# ASCII_14_Clocks.net
KiCad netlist of a schematic drawn in Altium Designer
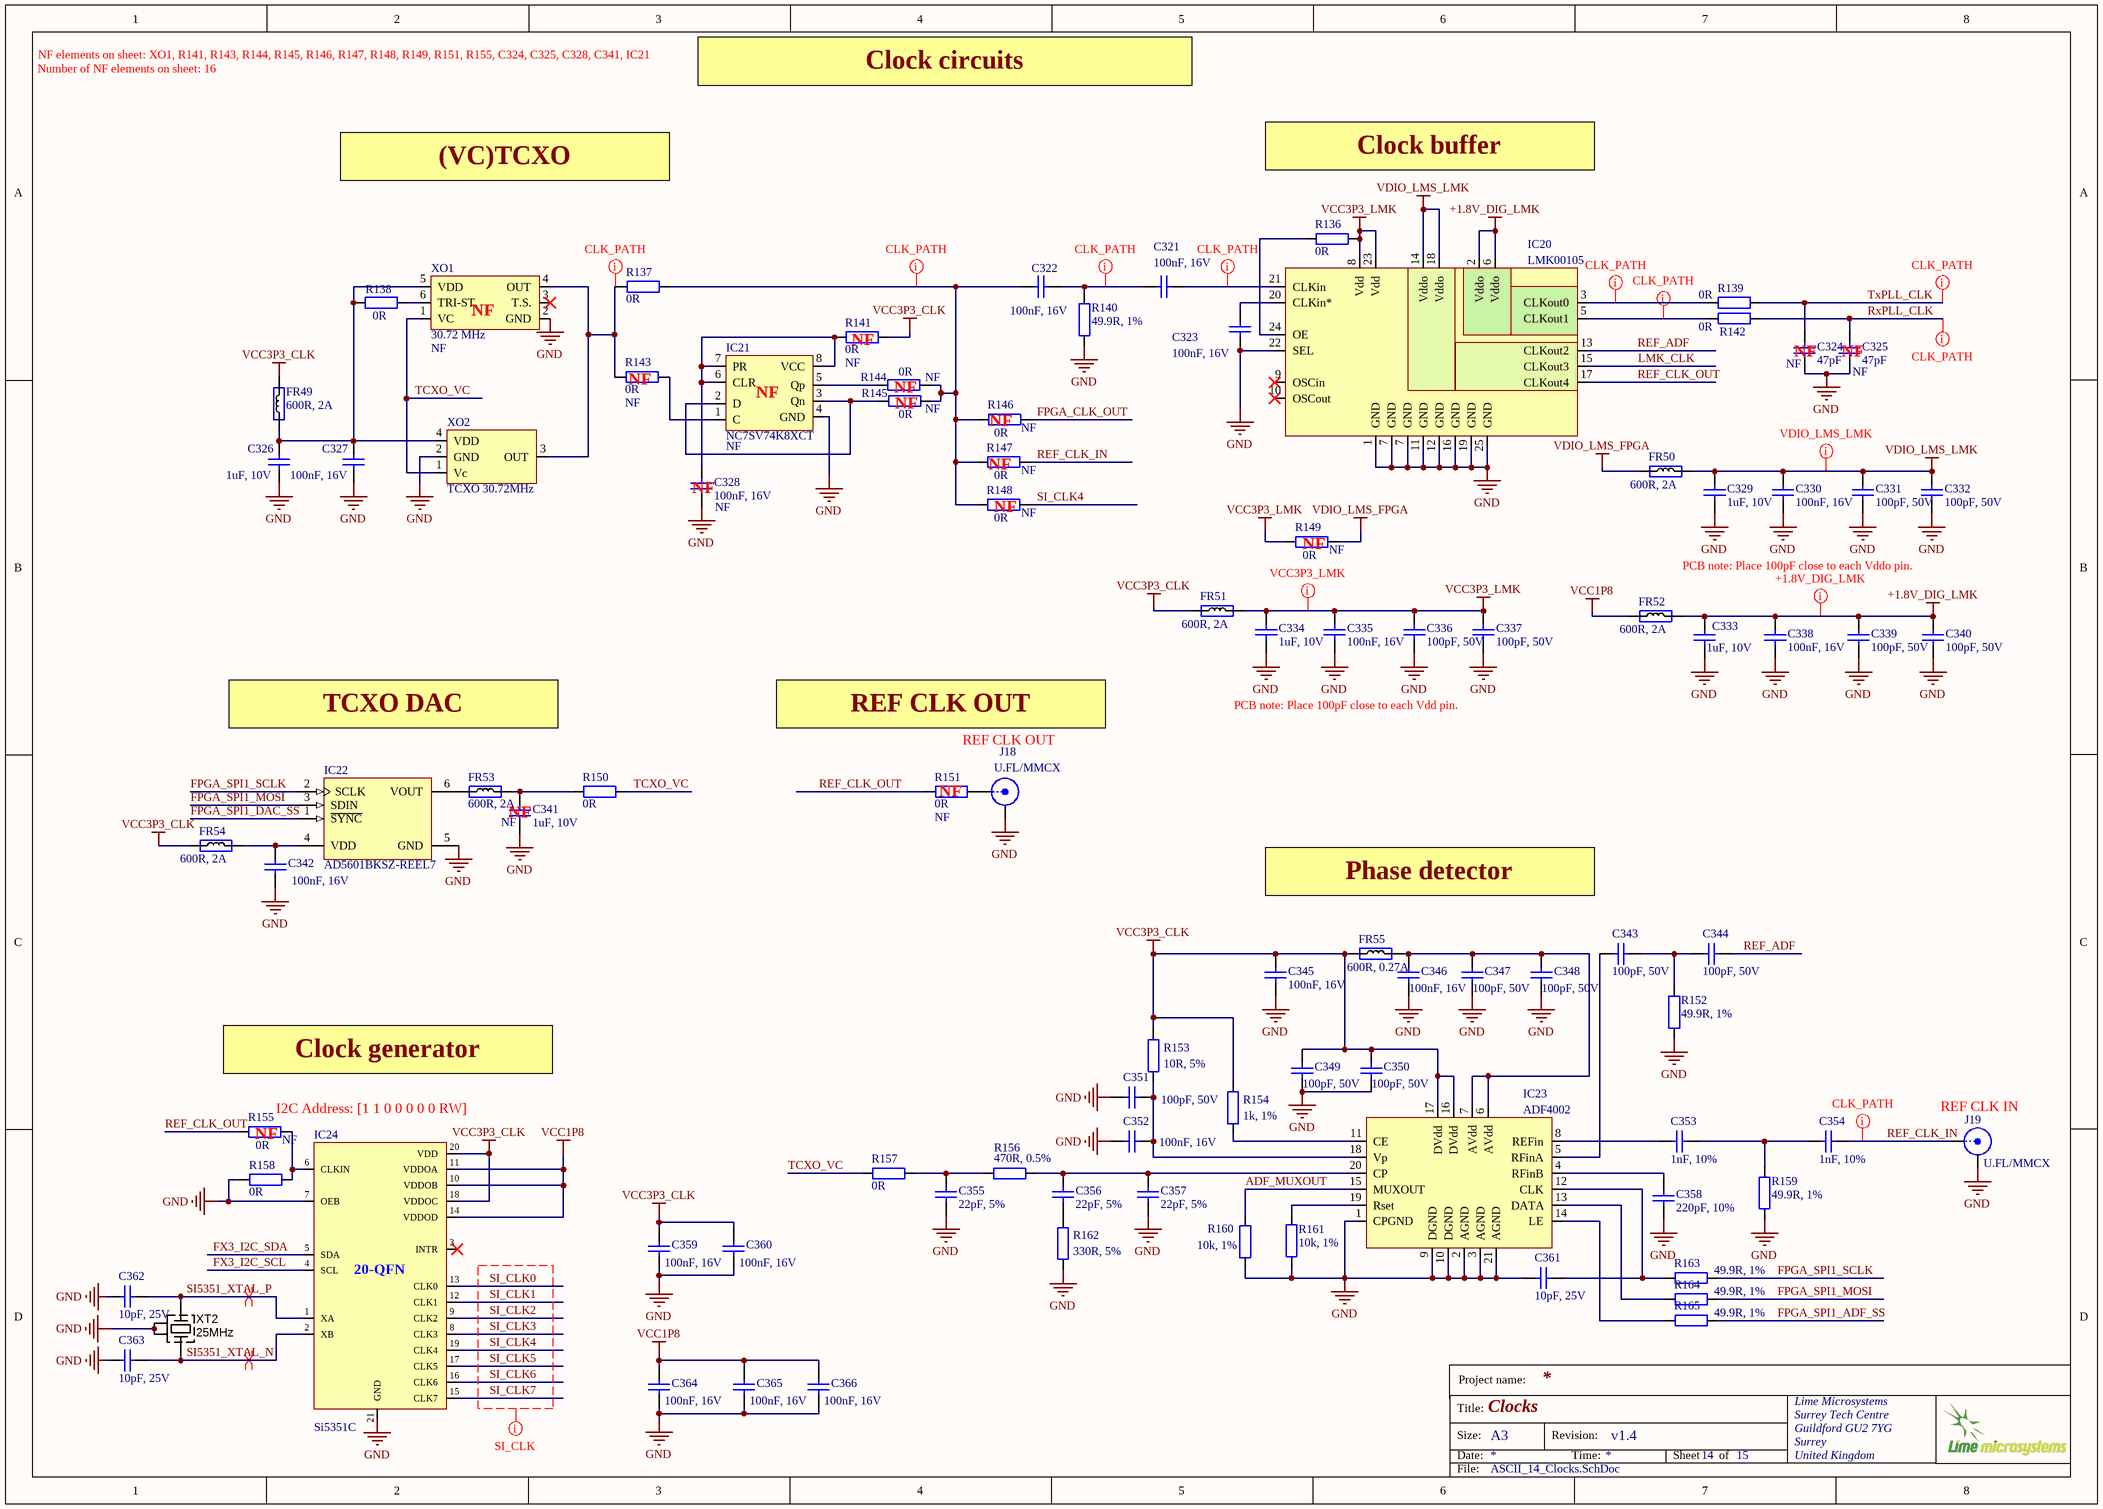
[diagram p0: ASCII_14_Clocks.SchDoc]

(export (version "E")
  (design (tool "Eeschema 10.0.6"))
  (components
    (comp (ref "C321")
      (value "100nF, 16V")
      (footprint "CAP0402")
      (fields
        (field (name "MANUFACTURER") "Murata Electronics")
        (field (name "TOLERANCE") "10 %")
        (field (name "MANUFACTURER PART NUMBER") "GRM155R71C104KA88D")
      )
      (libsource (lib "LimeMicroAltiumLib_schLib") (part "Cap_0402"))
    )
    (comp (ref "C322")
      (value "100nF, 16V")
      (footprint "CAP0402")
      (fields
        (field (name "MANUFACTURER") "Murata Electronics")
        (field (name "TOLERANCE") "10 %")
        (field (name "MANUFACTURER PART NUMBER") "GRM155R71C104KA88D")
      )
      (libsource (lib "LimeMicroAltiumLib_schLib") (part "Cap_0402"))
    )
    (comp (ref "C323")
      (value "100nF, 16V")
      (footprint "CAP0402")
      (fields
        (field (name "MANUFACTURER") "Murata Electronics")
        (field (name "TOLERANCE") "10 %")
        (field (name "MANUFACTURER PART NUMBER") "GRM155R71C104KA88D")
      )
      (libsource (lib "LimeMicroAltiumLib_schLib") (part "Cap_0402"))
    )
    (comp (ref "C324")
      (value "47pF")
      (footprint "CAP0402")
      (fields
        (field (name "TOLERANCE") "±1%")
        (field (name "MANUFACTURER") "TDK Corporation")
        (field (name "ASSEMBLY INFO") "NF")
      )
      (libsource (lib "LimeMicroAltiumLib_schLib") (part "Cap_0402"))
    )
    (comp (ref "C325")
      (value "47pF")
      (footprint "CAP0402")
      (fields
        (field (name "TOLERANCE") "±1%")
        (field (name "MANUFACTURER") "TDK Corporation")
        (field (name "ASSEMBLY INFO") "NF")
      )
      (libsource (lib "LimeMicroAltiumLib_schLib") (part "Cap_0402"))
    )
    (comp (ref "C326")
      (value "1uF, 10V")
      (footprint "CAP0402")
      (fields (field (name "MANUFACTURER") "TDK"))
      (libsource (lib "LimeMicroAltiumLib_schLib") (part "Cap_0402"))
    )
    (comp (ref "C327")
      (value "100nF, 16V")
      (footprint "CAP0402")
      (fields
        (field (name "MANUFACTURER") "Murata Electronics")
        (field (name "TOLERANCE") "10 %")
        (field (name "MANUFACTURER PART NUMBER") "GRM155R71C104KA88D")
      )
      (libsource (lib "LimeMicroAltiumLib_schLib") (part "Cap_0402"))
    )
    (comp (ref "C328")
      (value "100nF, 16V")
      (footprint "CAP0402")
      (fields
        (field (name "ASSEMBLY INFO") "NF")
        (field (name "MANUFACTURER") "Murata Electronics")
        (field (name "TOLERANCE") "10 %")
        (field (name "MANUFACTURER PART NUMBER") "GRM155R71C104KA88D")
      )
      (libsource (lib "LimeMicroAltiumLib_schLib") (part "Cap_0402"))
    )
    (comp (ref "C329")
      (value "1uF, 10V")
      (footprint "CAP0402")
      (fields (field (name "MANUFACTURER") "TDK"))
      (libsource (lib "LimeMicroAltiumLib_schLib") (part "Cap_0402"))
    )
    (comp (ref "C330")
      (value "100nF, 16V")
      (footprint "CAP0402")
      (fields
        (field (name "MANUFACTURER") "Murata Electronics")
        (field (name "TOLERANCE") "10 %")
        (field (name "MANUFACTURER PART NUMBER") "GRM155R71C104KA88D")
      )
      (libsource (lib "LimeMicroAltiumLib_schLib") (part "Cap_0402"))
    )
    (comp (ref "C331")
      (value "100pF, 50V")
      (footprint "CAP0402")
      (fields (field (name "MANUFACTURER") "Yageo") (field (name "TOLERANCE") "±5%"))
      (libsource (lib "LimeMicroAltiumLib_schLib") (part "Cap_0402"))
    )
    (comp (ref "C332")
      (value "100pF, 50V")
      (footprint "CAP0402")
      (fields (field (name "MANUFACTURER") "Yageo") (field (name "TOLERANCE") "±5%"))
      (libsource (lib "LimeMicroAltiumLib_schLib") (part "Cap_0402"))
    )
    (comp (ref "C333")
      (value "1uF, 10V")
      (footprint "CAP0402")
      (fields (field (name "MANUFACTURER") "TDK"))
      (libsource (lib "LimeMicroAltiumLib_schLib") (part "Cap_0402"))
    )
    (comp (ref "C334")
      (value "1uF, 10V")
      (footprint "CAP0402")
      (fields (field (name "MANUFACTURER") "TDK"))
      (libsource (lib "LimeMicroAltiumLib_schLib") (part "Cap_0402"))
    )
    (comp (ref "C335")
      (value "100nF, 16V")
      (footprint "CAP0402")
      (fields
        (field (name "MANUFACTURER") "Murata Electronics")
        (field (name "TOLERANCE") "10 %")
        (field (name "MANUFACTURER PART NUMBER") "GRM155R71C104KA88D")
      )
      (libsource (lib "LimeMicroAltiumLib_schLib") (part "Cap_0402"))
    )
    (comp (ref "C336")
      (value "100pF, 50V")
      (footprint "CAP0402")
      (fields (field (name "MANUFACTURER") "Yageo") (field (name "TOLERANCE") "±5%"))
      (libsource (lib "LimeMicroAltiumLib_schLib") (part "Cap_0402"))
    )
    (comp (ref "C337")
      (value "100pF, 50V")
      (footprint "CAP0402")
      (fields (field (name "MANUFACTURER") "Yageo") (field (name "TOLERANCE") "±5%"))
      (libsource (lib "LimeMicroAltiumLib_schLib") (part "Cap_0402"))
    )
    (comp (ref "C338")
      (value "100nF, 16V")
      (footprint "CAP0402")
      (fields
        (field (name "MANUFACTURER") "Murata Electronics")
        (field (name "TOLERANCE") "10 %")
        (field (name "MANUFACTURER PART NUMBER") "GRM155R71C104KA88D")
      )
      (libsource (lib "LimeMicroAltiumLib_schLib") (part "Cap_0402"))
    )
    (comp (ref "C339")
      (value "100pF, 50V")
      (footprint "CAP0402")
      (fields (field (name "MANUFACTURER") "Yageo") (field (name "TOLERANCE") "±5%"))
      (libsource (lib "LimeMicroAltiumLib_schLib") (part "Cap_0402"))
    )
    (comp (ref "C340")
      (value "100pF, 50V")
      (footprint "CAP0402")
      (fields (field (name "MANUFACTURER") "Yageo") (field (name "TOLERANCE") "±5%"))
      (libsource (lib "LimeMicroAltiumLib_schLib") (part "Cap_0402"))
    )
    (comp (ref "C341")
      (value "1uF, 10V")
      (footprint "CAP0402")
      (fields (field (name "ASSEMBLY INFO") "NF") (field (name "MANUFACTURER") "TDK"))
      (libsource (lib "LimeMicroAltiumLib_schLib") (part "Cap_0402"))
    )
    (comp (ref "C342")
      (value "100nF, 16V")
      (footprint "CAP0402")
      (fields
        (field (name "TOLERANCE") "10 %")
        (field (name "MANUFACTURER") "Murata Electronics")
        (field (name "MANUFACTURER PART NUMBER") "GRM155R71C104KA88D")
      )
      (libsource (lib "LimeFPGAboard_schLib") (part "Cap_0603"))
    )
    (comp (ref "C343")
      (value "100pF, 50V")
      (footprint "CAP0402")
      (fields (field (name "MANUFACTURER") "Yageo") (field (name "TOLERANCE") "±5%"))
      (libsource (lib "LimeMicroAltiumLib_schLib") (part "Cap_0402"))
    )
    (comp (ref "C344")
      (value "100pF, 50V")
      (footprint "CAP0402")
      (fields (field (name "MANUFACTURER") "Yageo") (field (name "TOLERANCE") "±5%"))
      (libsource (lib "LimeMicroAltiumLib_schLib") (part "Cap_0402"))
    )
    (comp (ref "C345")
      (value "100nF, 16V")
      (footprint "CAP0402")
      (fields
        (field (name "MANUFACTURER") "Murata Electronics")
        (field (name "TOLERANCE") "10 %")
        (field (name "MANUFACTURER PART NUMBER") "GRM155R71C104KA88D")
      )
      (libsource (lib "LimeMicroAltiumLib_schLib") (part "Cap_0402"))
    )
    (comp (ref "C346")
      (value "100nF, 16V")
      (footprint "CAP0402")
      (fields
        (field (name "MANUFACTURER") "Murata Electronics")
        (field (name "TOLERANCE") "10 %")
        (field (name "MANUFACTURER PART NUMBER") "GRM155R71C104KA88D")
      )
      (libsource (lib "LimeMicroAltiumLib_schLib") (part "Cap_0402"))
    )
    (comp (ref "C347")
      (value "100pF, 50V")
      (footprint "CAP0402")
      (fields (field (name "MANUFACTURER") "Yageo") (field (name "TOLERANCE") "±5%"))
      (libsource (lib "LimeMicroAltiumLib_schLib") (part "Cap_0402"))
    )
    (comp (ref "C348")
      (value "100pF, 50V")
      (footprint "CAP0402")
      (fields (field (name "MANUFACTURER") "Yageo") (field (name "TOLERANCE") "±5%"))
      (libsource (lib "LimeMicroAltiumLib_schLib") (part "Cap_0402"))
    )
    (comp (ref "C349")
      (value "100pF, 50V")
      (footprint "CAP0402")
      (fields (field (name "MANUFACTURER") "Yageo") (field (name "TOLERANCE") "±5%"))
      (libsource (lib "LimeMicroAltiumLib_schLib") (part "Cap_0402"))
    )
    (comp (ref "C350")
      (value "100pF, 50V")
      (footprint "CAP0402")
      (fields (field (name "MANUFACTURER") "Yageo") (field (name "TOLERANCE") "±5%"))
      (libsource (lib "LimeMicroAltiumLib_schLib") (part "Cap_0402"))
    )
    (comp (ref "C351")
      (value "100pF, 50V")
      (footprint "CAP0402")
      (fields (field (name "MANUFACTURER") "Yageo") (field (name "TOLERANCE") "±5%"))
      (libsource (lib "LimeMicroAltiumLib_schLib") (part "Cap_0402"))
    )
    (comp (ref "C352")
      (value "100nF, 16V")
      (footprint "CAP0402")
      (fields
        (field (name "MANUFACTURER") "Murata Electronics")
        (field (name "TOLERANCE") "10 %")
        (field (name "MANUFACTURER PART NUMBER") "GRM155R71C104KA88D")
      )
      (libsource (lib "LimeMicroAltiumLib_schLib") (part "Cap_0402"))
    )
    (comp (ref "C353")
      (value "1nF, 10%")
      (footprint "CAP0402")
      (fields (field (name "TOLERANCE") "10 %") (field (name "MANUFACTURER") "Murata Electronics"))
      (libsource (lib "LimeMicroAltiumLib_schLib") (part "Cap_0402"))
    )
    (comp (ref "C354")
      (value "1nF, 10%")
      (footprint "CAP0402")
      (fields (field (name "TOLERANCE") "10 %") (field (name "MANUFACTURER") "Murata Electronics"))
      (libsource (lib "LimeMicroAltiumLib_schLib") (part "Cap_0402"))
    )
    (comp (ref "C355")
      (value "22pF, 5%")
      (footprint "CAP0402")
      (fields (field (name "TOLERANCE") "±5%") (field (name "MANUFACTURER") "Yageo"))
      (libsource (lib "LimeMicroAltiumLib_schLib") (part "Cap_0402"))
    )
    (comp (ref "C356")
      (value "22pF, 5%")
      (footprint "CAP0402")
      (fields (field (name "TOLERANCE") "±5%") (field (name "MANUFACTURER") "Yageo"))
      (libsource (lib "LimeMicroAltiumLib_schLib") (part "Cap_0402"))
    )
    (comp (ref "C357")
      (value "22pF, 5%")
      (footprint "CAP0402")
      (fields (field (name "TOLERANCE") "±5%") (field (name "MANUFACTURER") "Yageo"))
      (libsource (lib "LimeMicroAltiumLib_schLib") (part "Cap_0402"))
    )
    (comp (ref "C358")
      (value "220pF, 10%")
      (footprint "CAP0402")
      (fields (field (name "MANUFACTURER") "Yageo") (field (name "TOLERANCE") "±10%"))
      (libsource (lib "LimeMicroAltiumLib_schLib") (part "Cap_0402"))
    )
    (comp (ref "C359")
      (value "100nF, 16V")
      (footprint "CAP0402")
      (fields
        (field (name "TOLERANCE") "10 %")
        (field (name "MANUFACTURER") "Murata Electronics")
        (field (name "MANUFACTURER PART NUMBER") "GRM155R71C104KA88D")
      )
      (libsource (lib "LimeFPGAboard_schLib") (part "Cap_0603"))
    )
    (comp (ref "C360")
      (value "100nF, 16V")
      (footprint "CAP0402")
      (fields
        (field (name "TOLERANCE") "10 %")
        (field (name "MANUFACTURER") "Murata Electronics")
        (field (name "MANUFACTURER PART NUMBER") "GRM155R71C104KA88D")
      )
      (libsource (lib "LimeFPGAboard_schLib") (part "Cap_0603"))
    )
    (comp (ref "C361")
      (value "10pF, 25V")
      (footprint "CAP0402")
      (fields (field (name "MANUFACTURER") "AVX"))
      (libsource (lib "LimeMicroAltiumLib_schLib") (part "Cap_0402"))
    )
    (comp (ref "C362")
      (value "10pF, 25V")
      (footprint "CAP0402")
      (fields (field (name "MANUFACTURER") "AVX"))
      (libsource (lib "LimeFPGAboard_schLib") (part "Cap_0402"))
    )
    (comp (ref "C363")
      (value "10pF, 25V")
      (footprint "CAP0402")
      (fields (field (name "MANUFACTURER") "AVX"))
      (libsource (lib "LimeFPGAboard_schLib") (part "Cap_0402"))
    )
    (comp (ref "C364")
      (value "100nF, 16V")
      (footprint "CAP0402")
      (fields
        (field (name "TOLERANCE") "10 %")
        (field (name "MANUFACTURER") "Murata Electronics")
        (field (name "MANUFACTURER PART NUMBER") "GRM155R71C104KA88D")
      )
      (libsource (lib "LimeFPGAboard_schLib") (part "Cap_0603"))
    )
    (comp (ref "C365")
      (value "100nF, 16V")
      (footprint "CAP0402")
      (fields
        (field (name "TOLERANCE") "10 %")
        (field (name "MANUFACTURER") "Murata Electronics")
        (field (name "MANUFACTURER PART NUMBER") "GRM155R71C104KA88D")
      )
      (libsource (lib "LimeFPGAboard_schLib") (part "Cap_0603"))
    )
    (comp (ref "C366")
      (value "100nF, 16V")
      (footprint "CAP0402")
      (fields
        (field (name "TOLERANCE") "10 %")
        (field (name "MANUFACTURER") "Murata Electronics")
        (field (name "MANUFACTURER PART NUMBER") "GRM155R71C104KA88D")
      )
      (libsource (lib "LimeFPGAboard_schLib") (part "Cap_0603"))
    )
    (comp (ref "FR49")
      (value "600R, 2A")
      (footprint "RES0805")
      (fields (field (name "MANUFACTURER") "TDK Corporation"))
      (libsource (lib "LimeMicroAltiumLib_schLib") (part "Ferrite"))
    )
    (comp (ref "FR50")
      (value "600R, 2A")
      (footprint "RES0805")
      (fields (field (name "MANUFACTURER") "TDK Corporation"))
      (libsource (lib "LimeMicroAltiumLib_schLib") (part "Ferrite"))
    )
    (comp (ref "FR51")
      (value "600R, 2A")
      (footprint "RES0805")
      (fields (field (name "MANUFACTURER") "TDK Corporation"))
      (libsource (lib "LimeMicroAltiumLib_schLib") (part "Ferrite"))
    )
    (comp (ref "FR52")
      (value "600R, 2A")
      (footprint "RES0805")
      (fields (field (name "MANUFACTURER") "TDK Corporation"))
      (libsource (lib "LimeMicroAltiumLib_schLib") (part "Ferrite"))
    )
    (comp (ref "FR53")
      (value "600R, 2A")
      (footprint "RES0805")
      (fields (field (name "MANUFACTURER") "TDK Corporation"))
      (libsource (lib "LimeMicroAltiumLib_schLib") (part "Ferrite"))
    )
    (comp (ref "FR54")
      (value "600R, 2A")
      (footprint "RES0805")
      (fields (field (name "MANUFACTURER") "TDK Corporation"))
      (libsource (lib "LimeMicroAltiumLib_schLib") (part "Ferrite"))
    )
    (comp (ref "FR55")
      (value "600R, 0.27A")
      (footprint "RES0201")
      (fields (field (name "MANUFACTURER") "Taiyo Yuden"))
      (libsource (lib "LimeMicroAltiumLib_schLib") (part "Ferrite"))
    )
    (comp (ref "IC20")
      (value "LMK00105")
      (footprint "LMK00105SQ")
      (fields (field (name "MANUFACTURER") "Texas Instruments"))
      (libsource (lib "LimeMicroAltiumLib_schLib") (part "LMK00105"))
    )
    (comp (ref "IC21")
      (value "NC7SV74K8XCT")
      (footprint "NC7SV74K8XCT")
      (fields (field (name "MANUFACTURER") "Fairchild Semiconductor") (field (name "ASSEMBLY INFO") "NF"))
      (libsource (lib "LimeMicroAltiumLib_schLib") (part "NC7SV74K8XCT"))
    )
    (comp (ref "IC22")
      (value "AD5601BKSZ-REEL7")
      (footprint "AD5601_SOT23-6")
      (fields (field (name "GENERIC PART NUMBER") "AD5601") (field (name "MANUFACTURER") "Analog Devices"))
      (libsource (lib "LimeMicroAltiumLib_schLib") (part "AD5601BKSZ-REEL7"))
    )
    (comp (ref "IC23")
      (value "ADF4002")
      (footprint "ADF4002")
      (fields (field (name "MANUFACTURER") "Analog Devices Inc"))
      (libsource (lib "LimeMicroAltiumLib_schLib") (part "ADF4002"))
    )
    (comp (ref "IC24")
      (value "Si5351C")
      (footprint "Si5351C_20QFN")
      (fields (field (name "MANUFACTURER") "Silicon Labs"))
      (libsource (lib "LimeFPGAboard_schLib") (part "Si5351C"))
    )
    (comp (ref "J18")
      (value "U.FL/MMCX")
      (footprint "MMCX_UFL_conn_u")
      (fields (field (name "MANUFACTURER") "Molex, LLC"))
      (libsource (lib "LimeMicroAltiumLib_schLib") (part "RF_IF_connector"))
    )
    (comp (ref "J19")
      (value "U.FL/MMCX")
      (footprint "MMCX_UFL_conn_u")
      (fields (field (name "MANUFACTURER") "Molex, LLC"))
      (libsource (lib "LimeMicroAltiumLib_schLib") (part "RF_IF_connector"))
    )
    (comp (ref "R136")
      (value "0R")
      (footprint "RES0402")
      (fields (field (name "MANUFACTURER") "Yageo") (field (name "TOLERANCE") "Jumper"))
      (libsource (lib "LimeMicroAltiumLib_schLib") (part "Res_0402"))
    )
    (comp (ref "R137")
      (value "0R")
      (footprint "RES0402")
      (fields (field (name "MANUFACTURER") "Yageo") (field (name "TOLERANCE") "Jumper"))
      (libsource (lib "LimeMicroAltiumLib_schLib") (part "Res_0402"))
    )
    (comp (ref "R138")
      (value "0R")
      (footprint "RES0402")
      (fields (field (name "MANUFACTURER") "Yageo") (field (name "TOLERANCE") "Jumper"))
      (libsource (lib "LimeMicroAltiumLib_schLib") (part "Res_0402"))
    )
    (comp (ref "R139")
      (value "0R")
      (footprint "RES0402")
      (fields (field (name "MANUFACTURER") "Yageo") (field (name "TOLERANCE") "Jumper"))
      (libsource (lib "LimeMicroAltiumLib_schLib") (part "Res_0402"))
    )
    (comp (ref "R140")
      (value "49.9R, 1%")
      (footprint "RES0402")
      (fields
        (field (name "TOLERANCE") "±1%")
        (field (name "MANUFACTURER") "Samsung Electro-Mechanics America, Inc.")
        (field (name "MANUFACTURER PART NUMBER") "RC1005F49R9CS")
      )
      (libsource (lib "LimeMicroAltiumLib_schLib") (part "Res_0402"))
    )
    (comp (ref "R141")
      (value "0R")
      (footprint "RES0402")
      (fields
        (field (name "ASSEMBLY INFO") "NF")
        (field (name "MANUFACTURER") "Yageo")
        (field (name "TOLERANCE") "Jumper")
      )
      (libsource (lib "LimeMicroAltiumLib_schLib") (part "Res_0402"))
    )
    (comp (ref "R142")
      (value "0R")
      (footprint "RES0402")
      (fields (field (name "MANUFACTURER") "Yageo") (field (name "TOLERANCE") "Jumper"))
      (libsource (lib "LimeMicroAltiumLib_schLib") (part "Res_0402"))
    )
    (comp (ref "R143")
      (value "0R")
      (footprint "RES0402")
      (fields
        (field (name "ASSEMBLY INFO") "NF")
        (field (name "MANUFACTURER") "Yageo")
        (field (name "TOLERANCE") "Jumper")
      )
      (libsource (lib "LimeMicroAltiumLib_schLib") (part "Res_0402"))
    )
    (comp (ref "R144")
      (value "0R")
      (footprint "RES0402")
      (fields
        (field (name "ASSEMBLY INFO") "NF")
        (field (name "MANUFACTURER") "Yageo")
        (field (name "TOLERANCE") "Jumper")
      )
      (libsource (lib "LimeMicroAltiumLib_schLib") (part "Res_0402"))
    )
    (comp (ref "R145")
      (value "0R")
      (footprint "RES0402")
      (fields
        (field (name "ASSEMBLY INFO") "NF")
        (field (name "MANUFACTURER") "Yageo")
        (field (name "TOLERANCE") "Jumper")
      )
      (libsource (lib "LimeMicroAltiumLib_schLib") (part "Res_0402"))
    )
    (comp (ref "R146")
      (value "0R")
      (footprint "RES0402")
      (fields
        (field (name "ASSEMBLY INFO") "NF")
        (field (name "MANUFACTURER") "Yageo")
        (field (name "TOLERANCE") "Jumper")
      )
      (libsource (lib "LimeMicroAltiumLib_schLib") (part "Res_0402"))
    )
    (comp (ref "R147")
      (value "0R")
      (footprint "RES0402")
      (fields
        (field (name "ASSEMBLY INFO") "NF")
        (field (name "MANUFACTURER") "Yageo")
        (field (name "TOLERANCE") "Jumper")
      )
      (libsource (lib "LimeMicroAltiumLib_schLib") (part "Res_0402"))
    )
    (comp (ref "R148")
      (value "0R")
      (footprint "RES0402")
      (fields
        (field (name "ASSEMBLY INFO") "NF")
        (field (name "MANUFACTURER") "Yageo")
        (field (name "TOLERANCE") "Jumper")
      )
      (libsource (lib "LimeMicroAltiumLib_schLib") (part "Res_0402"))
    )
    (comp (ref "R149")
      (value "0R")
      (footprint "RES0402")
      (fields
        (field (name "ASSEMBLY INFO") "NF")
        (field (name "MANUFACTURER") "Yageo")
        (field (name "TOLERANCE") "Jumper")
      )
      (libsource (lib "LimeMicroAltiumLib_schLib") (part "Res_0402"))
    )
    (comp (ref "R150")
      (value "0R")
      (footprint "RES0402")
      (fields (field (name "MANUFACTURER") "Yageo") (field (name "TOLERANCE") "Jumper"))
      (libsource (lib "LimeMicroAltiumLib_schLib") (part "Res_0402"))
    )
    (comp (ref "R151")
      (value "0R")
      (footprint "RES0402")
      (fields
        (field (name "ASSEMBLY INFO") "NF")
        (field (name "MANUFACTURER") "Yageo")
        (field (name "TOLERANCE") "Jumper")
      )
      (libsource (lib "LimeMicroAltiumLib_schLib") (part "Res_0402"))
    )
    (comp (ref "R152")
      (value "49.9R, 1%")
      (footprint "RES0402")
      (fields
        (field (name "TOLERANCE") "±1%")
        (field (name "MANUFACTURER") "Samsung Electro-Mechanics America, Inc.")
        (field (name "MANUFACTURER PART NUMBER") "RC1005F49R9CS")
      )
      (libsource (lib "LimeMicroAltiumLib_schLib") (part "Res_0402"))
    )
    (comp (ref "R153")
      (value "10R, 5%")
      (footprint "RES0402")
      (fields (field (name "TOLERANCE") "±5%") (field (name "MANUFACTURER") "Yageo"))
      (libsource (lib "LimeMicroAltiumLib_schLib") (part "Res_0402"))
    )
    (comp (ref "R154")
      (value "1k, 1%")
      (footprint "RES0402")
      (fields (field (name "MANUFACTURER") "Stackpole Electronics Inc") (field (name "TOLERANCE") "±1%"))
      (libsource (lib "LimeMicroAltiumLib_schLib") (part "Res_0402"))
    )
    (comp (ref "R155")
      (value "0R")
      (footprint "RES0402")
      (fields
        (field (name "ASSEMBLY INFO") "NF")
        (field (name "MANUFACTURER") "Yageo")
        (field (name "TOLERANCE") "Jumper")
      )
      (libsource (lib "LimeMicroAltiumLib_schLib") (part "Res_0402"))
    )
    (comp (ref "R156")
      (value "470R, 0.5%")
      (footprint "RES0402")
      (fields
        (field (name "TOLERANCE") "±0.5%")
        (field (name "MANUFACTURER") "Panasonic Electronic Components")
      )
      (libsource (lib "LimeMicroAltiumLib_schLib") (part "Res_0402"))
    )
    (comp (ref "R157")
      (value "0R")
      (footprint "RES0402")
      (fields (field (name "MANUFACTURER") "Yageo") (field (name "TOLERANCE") "Jumper"))
      (libsource (lib "LimeMicroAltiumLib_schLib") (part "Res_0402"))
    )
    (comp (ref "R158")
      (value "0R")
      (footprint "RES0402")
      (fields (field (name "MANUFACTURER") "Yageo") (field (name "TOLERANCE") "Jumper"))
      (libsource (lib "LimeMicroAltiumLib_schLib") (part "Res_0402"))
    )
    (comp (ref "R159")
      (value "49.9R, 1%")
      (footprint "RES0402")
      (fields
        (field (name "TOLERANCE") "±1%")
        (field (name "MANUFACTURER") "Samsung Electro-Mechanics America, Inc.")
        (field (name "MANUFACTURER PART NUMBER") "RC1005F49R9CS")
      )
      (libsource (lib "LimeMicroAltiumLib_schLib") (part "Res_0402"))
    )
    (comp (ref "R160")
      (value "10k, 1%")
      (footprint "RES0402")
      (fields (field (name "MANUFACTURER") "Yageo") (field (name "TOLERANCE") "±1%"))
      (libsource (lib "LimeMicroAltiumLib_schLib") (part "Res_0402"))
    )
    (comp (ref "R161")
      (value "10k, 1%")
      (footprint "RES0402")
      (fields (field (name "MANUFACTURER") "Yageo") (field (name "TOLERANCE") "±1%"))
      (libsource (lib "LimeMicroAltiumLib_schLib") (part "Res_0402"))
    )
    (comp (ref "R162")
      (value "330R, 5%")
      (footprint "RES0402")
      (fields (field (name "MANUFACTURER") "Yageo") (field (name "TOLERANCE") "±5%"))
      (libsource (lib "LimeMicroAltiumLib_schLib") (part "Res_0402"))
    )
    (comp (ref "R163")
      (value "49.9R, 1%")
      (footprint "RES0402")
      (fields
        (field (name "TOLERANCE") "±1%")
        (field (name "MANUFACTURER") "Samsung Electro-Mechanics America, Inc.")
        (field (name "MANUFACTURER PART NUMBER") "RC1005F49R9CS")
      )
      (libsource (lib "LimeMicroAltiumLib_schLib") (part "Res_0402"))
    )
    (comp (ref "R164")
      (value "49.9R, 1%")
      (footprint "RES0402")
      (fields
        (field (name "TOLERANCE") "±1%")
        (field (name "MANUFACTURER") "Samsung Electro-Mechanics America, Inc.")
        (field (name "MANUFACTURER PART NUMBER") "RC1005F49R9CS")
      )
      (libsource (lib "LimeMicroAltiumLib_schLib") (part "Res_0402"))
    )
    (comp (ref "R165")
      (value "49.9R, 1%")
      (footprint "RES0402")
      (fields
        (field (name "TOLERANCE") "±1%")
        (field (name "MANUFACTURER") "Samsung Electro-Mechanics America, Inc.")
        (field (name "MANUFACTURER PART NUMBER") "RC1005F49R9CS")
      )
      (libsource (lib "LimeMicroAltiumLib_schLib") (part "Res_0402"))
    )
    (comp (ref "XO1")
      (value "30.72 MHz")
      (footprint "RAKON_RPT7050A")
      (fields (field (name "ASSEMBLY INFO") "NF") (field (name "MANUFACTURER") "Rakon"))
      (libsource (lib "LimeMicroAltiumLib_schLib") (part "RPT7050A"))
    )
    (comp (ref "XO2")
      (value "TCXO 30.72MHz")
      (footprint "RAKON_TXCO")
      (fields (field (name "MANUFACTURER") "Rakon"))
      (libsource (lib "LimeMicroAltiumLib_schLib") (part "TXCO"))
    )
    (comp (ref "XT2")
      (value "25MHz")
      (footprint "CRYSTAL_4-LCC")
      (description "Oscillator Crystal 25 MHz")
      (fields (field (name "MANUFACTURER") "ABRACON"))
      (libsource (lib "LimeFPGAboard_schLib") (part "CRYSTAL_19M2"))
    )
  )
  (nets
    (net (code "1") (name "+1.8V_DIG_LMK") (class "Default")
      (node (ref "C333") (pin "2") (pinfunction "2_2") (pintype "passive"))
      (node (ref "C338") (pin "2") (pinfunction "2_2") (pintype "passive"))
      (node (ref "C339") (pin "2") (pinfunction "2_2") (pintype "passive"))
      (node (ref "C340") (pin "2") (pinfunction "2_2") (pintype "passive"))
      (node (ref "FR52") (pin "2") (pinfunction "2_2") (pintype "passive"))
      (node (ref "IC20") (pin "2") (pinfunction "Vddo_2") (pintype "passive"))
      (node (ref "IC20") (pin "6") (pinfunction "Vddo_6") (pintype "passive"))
    )
    (net (code "2") (name "/ADF_MUXOUT") (class "Default")
      (node (ref "IC23") (pin "15") (pinfunction "MUXOUT_15") (pintype "passive"))
      (node (ref "R160") (pin "1") (pinfunction "1_1") (pintype "passive"))
    )
    (net (code "3") (name "/FPGA_CLK_OUT") (class "Default")
      (node (ref "R146") (pin "1") (pinfunction "1_1") (pintype "passive"))
    )
    (net (code "4") (name "/FPGA_SPI1_ADF_SS") (class "Default")
      (node (ref "R165") (pin "1") (pinfunction "1_1") (pintype "passive"))
    )
    (net (code "5") (name "/FPGA_SPI1_DAC_SS") (class "Default")
      (node (ref "IC22") (pin "1") (pinfunction "~{SYNC}_1") (pintype "input"))
    )
    (net (code "6") (name "/FPGA_SPI1_MOSI") (class "Default")
      (node (ref "IC22") (pin "3") (pinfunction "SDIN_3") (pintype "input"))
      (node (ref "R164") (pin "1") (pinfunction "1_1") (pintype "passive"))
    )
    (net (code "7") (name "/FPGA_SPI1_SCLK") (class "Default")
      (node (ref "IC22") (pin "2") (pinfunction "SCLK_2") (pintype "input"))
      (node (ref "R163") (pin "1") (pinfunction "1_1") (pintype "passive"))
    )
    (net (code "8") (name "/FX3_I2C_SCL") (class "Default")
      (node (ref "IC24") (pin "4") (pinfunction "SCL_4") (pintype "passive"))
    )
    (net (code "9") (name "/FX3_I2C_SDA") (class "Default")
      (node (ref "IC24") (pin "5") (pinfunction "SDA_5") (pintype "passive"))
    )
    (net (code "10") (name "/LMK_CLK") (class "Default")
      (node (ref "IC20") (pin "15") (pinfunction "CLKout3_15") (pintype "passive"))
    )
    (net (code "11") (name "/REF_ADF") (class "Default")
      (node (ref "C344") (pin "2") (pinfunction "2_2") (pintype "passive"))
      (node (ref "IC20") (pin "13") (pinfunction "CLKout2_13") (pintype "passive"))
    )
    (net (code "12") (name "/REF_CLK_IN") (class "Default")
      (node (ref "C354") (pin "1") (pinfunction "1_1") (pintype "passive"))
      (node (ref "J19") (pin "1") (pinfunction "X_1") (pintype "passive"))
      (node (ref "R147") (pin "2") (pinfunction "2_2") (pintype "passive"))
    )
    (net (code "13") (name "/REF_CLK_OUT") (class "Default")
      (node (ref "IC20") (pin "17") (pinfunction "CLKout4_17") (pintype "passive"))
      (node (ref "R151") (pin "2") (pinfunction "2_2") (pintype "passive"))
      (node (ref "R155") (pin "1") (pinfunction "1_1") (pintype "passive"))
    )
    (net (code "14") (name "/RxPLL_CLK") (class "Default")
      (node (ref "C325") (pin "2") (pinfunction "2_2") (pintype "passive"))
      (node (ref "R142") (pin "1") (pinfunction "1_1") (pintype "passive"))
    )
    (net (code "15") (name "/SI5351_XTAL_N") (class "Default")
      (node (ref "C363") (pin "2") (pinfunction "2_2") (pintype "passive"))
      (node (ref "IC24") (pin "2") (pinfunction "XB_2") (pintype "passive"))
      (node (ref "XT2") (pin "3") (pinfunction "X_3") (pintype "passive"))
    )
    (net (code "16") (name "/SI5351_XTAL_P") (class "Default")
      (node (ref "C362") (pin "2") (pinfunction "2_2") (pintype "passive"))
      (node (ref "IC24") (pin "1") (pinfunction "XA_1") (pintype "passive"))
      (node (ref "XT2") (pin "1") (pinfunction "X_1") (pintype "passive"))
    )
    (net (code "17") (name "/SI_CLK0") (class "Default")
      (node (ref "IC24") (pin "13") (pinfunction "CLK0_13") (pintype "passive"))
    )
    (net (code "18") (name "/SI_CLK1") (class "Default")
      (node (ref "IC24") (pin "12") (pinfunction "CLK1_12") (pintype "passive"))
    )
    (net (code "19") (name "/SI_CLK2") (class "Default")
      (node (ref "IC24") (pin "9") (pinfunction "CLK2_9") (pintype "passive"))
    )
    (net (code "20") (name "/SI_CLK3") (class "Default")
      (node (ref "IC24") (pin "8") (pinfunction "CLK3_8") (pintype "passive"))
    )
    (net (code "21") (name "/SI_CLK4") (class "Default")
      (node (ref "IC24") (pin "19") (pinfunction "CLK4_19") (pintype "passive"))
      (node (ref "R148") (pin "2") (pinfunction "2_2") (pintype "passive"))
    )
    (net (code "22") (name "/SI_CLK5") (class "Default")
      (node (ref "IC24") (pin "17") (pinfunction "CLK5_17") (pintype "passive"))
    )
    (net (code "23") (name "/SI_CLK6") (class "Default")
      (node (ref "IC24") (pin "16") (pinfunction "CLK6_16") (pintype "passive"))
    )
    (net (code "24") (name "/SI_CLK7") (class "Default")
      (node (ref "IC24") (pin "15") (pinfunction "CLK7_15") (pintype "passive"))
    )
    (net (code "25") (name "/TCXO_VC") (class "Default")
      (node (ref "R150") (pin "1") (pinfunction "1_1") (pintype "passive"))
      (node (ref "R157") (pin "2") (pinfunction "2_2") (pintype "passive"))
      (node (ref "XO1") (pin "1") (pinfunction "VC_1") (pintype "passive"))
      (node (ref "XO2") (pin "1") (pinfunction "Vc_1") (pintype "passive"))
    )
    (net (code "26") (name "/TxPLL_CLK") (class "Default")
      (node (ref "C324") (pin "2") (pinfunction "2_2") (pintype "passive"))
      (node (ref "R139") (pin "1") (pinfunction "1_1") (pintype "passive"))
    )
    (net (code "27") (name "GND") (class "Default")
      (node (ref "C323") (pin "1") (pinfunction "1_1") (pintype "passive"))
      (node (ref "C324") (pin "1") (pinfunction "1_1") (pintype "passive"))
      (node (ref "C325") (pin "1") (pinfunction "1_1") (pintype "passive"))
      (node (ref "C326") (pin "1") (pinfunction "1_1") (pintype "passive"))
      (node (ref "C327") (pin "1") (pinfunction "1_1") (pintype "passive"))
      (node (ref "C328") (pin "1") (pinfunction "1_1") (pintype "passive"))
      (node (ref "C329") (pin "1") (pinfunction "1_1") (pintype "passive"))
      (node (ref "C330") (pin "1") (pinfunction "1_1") (pintype "passive"))
      (node (ref "C331") (pin "1") (pinfunction "1_1") (pintype "passive"))
      (node (ref "C332") (pin "1") (pinfunction "1_1") (pintype "passive"))
      (node (ref "C333") (pin "1") (pinfunction "1_1") (pintype "passive"))
      (node (ref "C334") (pin "1") (pinfunction "1_1") (pintype "passive"))
      (node (ref "C335") (pin "1") (pinfunction "1_1") (pintype "passive"))
      (node (ref "C336") (pin "1") (pinfunction "1_1") (pintype "passive"))
      (node (ref "C337") (pin "1") (pinfunction "1_1") (pintype "passive"))
      (node (ref "C338") (pin "1") (pinfunction "1_1") (pintype "passive"))
      (node (ref "C339") (pin "1") (pinfunction "1_1") (pintype "passive"))
      (node (ref "C340") (pin "1") (pinfunction "1_1") (pintype "passive"))
      (node (ref "C341") (pin "1") (pinfunction "1_1") (pintype "passive"))
      (node (ref "C342") (pin "2") (pinfunction "2_2") (pintype "passive"))
      (node (ref "C345") (pin "1") (pinfunction "1_1") (pintype "passive"))
      (node (ref "C346") (pin "1") (pinfunction "1_1") (pintype "passive"))
      (node (ref "C347") (pin "2") (pinfunction "2_2") (pintype "passive"))
      (node (ref "C348") (pin "2") (pinfunction "2_2") (pintype "passive"))
      (node (ref "C349") (pin "2") (pinfunction "2_2") (pintype "passive"))
      (node (ref "C350") (pin "2") (pinfunction "2_2") (pintype "passive"))
      (node (ref "C351") (pin "1") (pinfunction "1_1") (pintype "passive"))
      (node (ref "C352") (pin "2") (pinfunction "2_2") (pintype "passive"))
      (node (ref "C355") (pin "1") (pinfunction "1_1") (pintype "passive"))
      (node (ref "C357") (pin "1") (pinfunction "1_1") (pintype "passive"))
      (node (ref "C358") (pin "2") (pinfunction "2_2") (pintype "passive"))
      (node (ref "C359") (pin "2") (pinfunction "2_2") (pintype "passive"))
      (node (ref "C360") (pin "2") (pinfunction "2_2") (pintype "passive"))
      (node (ref "C361") (pin "1") (pinfunction "1_1") (pintype "passive"))
      (node (ref "C362") (pin "1") (pinfunction "1_1") (pintype "passive"))
      (node (ref "C363") (pin "1") (pinfunction "1_1") (pintype "passive"))
      (node (ref "C364") (pin "2") (pinfunction "2_2") (pintype "passive"))
      (node (ref "C365") (pin "2") (pinfunction "2_2") (pintype "passive"))
      (node (ref "C366") (pin "2") (pinfunction "2_2") (pintype "passive"))
      (node (ref "IC20") (pin "1") (pinfunction "GND_1") (pintype "passive"))
      (node (ref "IC20") (pin "11") (pinfunction "GND_11") (pintype "passive"))
      (node (ref "IC20") (pin "12") (pinfunction "GND_12") (pintype "passive"))
      (node (ref "IC20") (pin "16") (pinfunction "GND_16") (pintype "passive"))
      (node (ref "IC20") (pin "19") (pinfunction "GND_19") (pintype "passive"))
      (node (ref "IC20") (pin "22") (pinfunction "SEL_22") (pintype "passive"))
      (node (ref "IC20") (pin "25") (pinfunction "GND_25") (pintype "passive"))
      (node (ref "IC20") (pin "7") (pinfunction "GND_7") (pintype "passive"))
      (node (ref "IC21") (pin "4") (pinfunction "GND_4") (pintype "passive"))
      (node (ref "IC22") (pin "5") (pinfunction "GND_5") (pintype "power_in"))
      (node (ref "IC23") (pin "1") (pinfunction "CPGND_1") (pintype "passive"))
      (node (ref "IC23") (pin "10") (pinfunction "DGND_10") (pintype "passive"))
      (node (ref "IC23") (pin "2") (pinfunction "AGND_2") (pintype "passive"))
      (node (ref "IC23") (pin "21") (pinfunction "AGND_21") (pintype "passive"))
      (node (ref "IC23") (pin "3") (pinfunction "AGND_3") (pintype "passive"))
      (node (ref "IC23") (pin "9") (pinfunction "DGND_9") (pintype "passive"))
      (node (ref "IC24") (pin "21") (pinfunction "GND_21") (pintype "passive"))
      (node (ref "IC24") (pin "7") (pinfunction "OEB_7") (pintype "passive"))
      (node (ref "J18") (pin "2") (pinfunction "Y_2") (pintype "passive"))
      (node (ref "J19") (pin "2") (pinfunction "Y_2") (pintype "passive"))
      (node (ref "R140") (pin "1") (pinfunction "1_1") (pintype "passive"))
      (node (ref "R152") (pin "1") (pinfunction "1_1") (pintype "passive"))
      (node (ref "R158") (pin "2") (pinfunction "2_2") (pintype "passive"))
      (node (ref "R159") (pin "1") (pinfunction "1_1") (pintype "passive"))
      (node (ref "R160") (pin "2") (pinfunction "2_2") (pintype "passive"))
      (node (ref "R161") (pin "2") (pinfunction "2_2") (pintype "passive"))
      (node (ref "R162") (pin "1") (pinfunction "1_1") (pintype "passive"))
      (node (ref "XO1") (pin "2") (pinfunction "GND_2") (pintype "passive"))
      (node (ref "XO2") (pin "2") (pinfunction "GND_2") (pintype "passive"))
      (node (ref "XT2") (pin "2") (pinfunction "GND_2") (pintype "passive"))
      (node (ref "XT2") (pin "4") (pinfunction "GND_4") (pintype "passive"))
    )
    (net (code "28") (name "Net-(C321-Pad2)") (class "Default")
      (node (ref "C321") (pin "2") (pinfunction "2_2") (pintype "passive"))
      (node (ref "C322") (pin "1") (pinfunction "1_1") (pintype "passive"))
      (node (ref "R140") (pin "2") (pinfunction "2_2") (pintype "passive"))
    )
    (net (code "29") (name "Net-(C322-Pad2)") (class "Default")
      (node (ref "C322") (pin "2") (pinfunction "2_2") (pintype "passive"))
      (node (ref "R137") (pin "1") (pinfunction "1_1") (pintype "passive"))
      (node (ref "R144") (pin "1") (pinfunction "1_1") (pintype "passive"))
      (node (ref "R145") (pin "1") (pinfunction "1_1") (pintype "passive"))
      (node (ref "R146") (pin "2") (pinfunction "2_2") (pintype "passive"))
      (node (ref "R147") (pin "1") (pinfunction "1_1") (pintype "passive"))
      (node (ref "R148") (pin "1") (pinfunction "1_1") (pintype "passive"))
    )
    (net (code "30") (name "Net-(C341-Pad2)") (class "Default")
      (node (ref "C341") (pin "2") (pinfunction "2_2") (pintype "passive"))
      (node (ref "FR53") (pin "2") (pinfunction "2_2") (pintype "passive"))
      (node (ref "R150") (pin "2") (pinfunction "2_2") (pintype "passive"))
    )
    (net (code "31") (name "Net-(C343-Pad2)") (class "Default")
      (node (ref "C343") (pin "2") (pinfunction "2_2") (pintype "passive"))
      (node (ref "C344") (pin "1") (pinfunction "1_1") (pintype "passive"))
      (node (ref "R152") (pin "2") (pinfunction "2_2") (pintype "passive"))
    )
    (net (code "32") (name "Net-(C346-Pad2)") (class "Default")
      (node (ref "C346") (pin "2") (pinfunction "2_2") (pintype "passive"))
      (node (ref "C347") (pin "1") (pinfunction "1_1") (pintype "passive"))
      (node (ref "C348") (pin "1") (pinfunction "1_1") (pintype "passive"))
      (node (ref "FR55") (pin "2") (pinfunction "2_2") (pintype "passive"))
      (node (ref "IC23") (pin "6") (pinfunction "AVdd_6") (pintype "passive"))
      (node (ref "IC23") (pin "7") (pinfunction "AVdd_7") (pintype "passive"))
    )
    (net (code "33") (name "Net-(C353-Pad1)") (class "Default")
      (node (ref "C353") (pin "1") (pinfunction "1_1") (pintype "passive"))
      (node (ref "C354") (pin "2") (pinfunction "2_2") (pintype "passive"))
      (node (ref "R159") (pin "2") (pinfunction "2_2") (pintype "passive"))
    )
    (net (code "34") (name "Net-(C355-Pad2)") (class "Default")
      (node (ref "C355") (pin "2") (pinfunction "2_2") (pintype "passive"))
      (node (ref "R156") (pin "2") (pinfunction "2_2") (pintype "passive"))
      (node (ref "R157") (pin "1") (pinfunction "1_1") (pintype "passive"))
    )
    (net (code "35") (name "Net-(C356-Pad1)") (class "Default")
      (node (ref "C356") (pin "1") (pinfunction "1_1") (pintype "passive"))
      (node (ref "R162") (pin "2") (pinfunction "2_2") (pintype "passive"))
    )
    (net (code "36") (name "Net-(IC20-CLKin)") (class "Default")
      (node (ref "C321") (pin "1") (pinfunction "1_1") (pintype "passive"))
      (node (ref "IC20") (pin "21") (pinfunction "CLKin_21") (pintype "passive"))
    )
    (net (code "37") (name "Net-(IC20-CLKin*)") (class "Default")
      (node (ref "C323") (pin "2") (pinfunction "2_2") (pintype "passive"))
      (node (ref "IC20") (pin "20") (pinfunction "CLKin*_20") (pintype "passive"))
    )
    (net (code "38") (name "Net-(IC20-CLKout0)") (class "Default")
      (node (ref "IC20") (pin "3") (pinfunction "CLKout0_3") (pintype "passive"))
      (node (ref "R139") (pin "2") (pinfunction "2_2") (pintype "passive"))
    )
    (net (code "39") (name "Net-(IC20-CLKout1)") (class "Default")
      (node (ref "IC20") (pin "5") (pinfunction "CLKout1_5") (pintype "passive"))
      (node (ref "R142") (pin "2") (pinfunction "2_2") (pintype "passive"))
    )
    (net (code "40") (name "Net-(IC20-OE)") (class "Default")
      (node (ref "IC20") (pin "24") (pinfunction "OE_24") (pintype "passive"))
      (node (ref "R136") (pin "1") (pinfunction "1_1") (pintype "passive"))
    )
    (net (code "41") (name "Net-(IC21-C)") (class "Default")
      (node (ref "IC21") (pin "1") (pinfunction "C_1") (pintype "passive"))
      (node (ref "R143") (pin "1") (pinfunction "1_1") (pintype "passive"))
    )
    (net (code "42") (name "Net-(IC21-CLR)") (class "Default")
      (node (ref "C328") (pin "2") (pinfunction "2_2") (pintype "passive"))
      (node (ref "IC21") (pin "6") (pinfunction "CLR_6") (pintype "passive"))
      (node (ref "IC21") (pin "7") (pinfunction "PR_7") (pintype "passive"))
      (node (ref "IC21") (pin "8") (pinfunction "VCC_8") (pintype "passive"))
      (node (ref "R141") (pin "2") (pinfunction "2_2") (pintype "passive"))
    )
    (net (code "43") (name "Net-(IC21-D)") (class "Default")
      (node (ref "IC21") (pin "2") (pinfunction "D_2") (pintype "passive"))
      (node (ref "IC21") (pin "3") (pinfunction "Qn_3") (pintype "passive"))
      (node (ref "R145") (pin "2") (pinfunction "2_2") (pintype "passive"))
    )
    (net (code "44") (name "Net-(IC21-Qp)") (class "Default")
      (node (ref "IC21") (pin "5") (pinfunction "Qp_5") (pintype "passive"))
      (node (ref "R144") (pin "2") (pinfunction "2_2") (pintype "passive"))
    )
    (net (code "45") (name "Net-(IC22-VDD)") (class "Default")
      (node (ref "C342") (pin "1") (pinfunction "1_1") (pintype "passive"))
      (node (ref "FR54") (pin "2") (pinfunction "2_2") (pintype "passive"))
      (node (ref "IC22") (pin "4") (pinfunction "VDD_4") (pintype "power_in"))
    )
    (net (code "46") (name "Net-(IC22-VOUT)") (class "Default")
      (node (ref "FR53") (pin "1") (pinfunction "1_1") (pintype "passive"))
      (node (ref "IC22") (pin "6") (pinfunction "VOUT_6") (pintype "tri_state"))
    )
    (net (code "47") (name "Net-(IC23-CE)") (class "Default")
      (node (ref "IC23") (pin "11") (pinfunction "CE_11") (pintype "passive"))
      (node (ref "R154") (pin "1") (pinfunction "1_1") (pintype "passive"))
    )
    (net (code "48") (name "Net-(IC23-CLK)") (class "Default")
      (node (ref "C361") (pin "2") (pinfunction "2_2") (pintype "passive"))
      (node (ref "IC23") (pin "12") (pinfunction "CLK_12") (pintype "passive"))
      (node (ref "R163") (pin "2") (pinfunction "2_2") (pintype "passive"))
    )
    (net (code "49") (name "Net-(IC23-CP)") (class "Default")
      (node (ref "C356") (pin "2") (pinfunction "2_2") (pintype "passive"))
      (node (ref "C357") (pin "2") (pinfunction "2_2") (pintype "passive"))
      (node (ref "IC23") (pin "20") (pinfunction "CP_20") (pintype "passive"))
      (node (ref "R156") (pin "1") (pinfunction "1_1") (pintype "passive"))
    )
    (net (code "50") (name "Net-(IC23-DATA)") (class "Default")
      (node (ref "IC23") (pin "13") (pinfunction "DATA_13") (pintype "passive"))
      (node (ref "R164") (pin "2") (pinfunction "2_2") (pintype "passive"))
    )
    (net (code "51") (name "Net-(IC23-LE)") (class "Default")
      (node (ref "IC23") (pin "14") (pinfunction "LE_14") (pintype "passive"))
      (node (ref "R165") (pin "2") (pinfunction "2_2") (pintype "passive"))
    )
    (net (code "52") (name "Net-(IC23-REFin)") (class "Default")
      (node (ref "C353") (pin "2") (pinfunction "2_2") (pintype "passive"))
      (node (ref "IC23") (pin "8") (pinfunction "REFin_8") (pintype "passive"))
    )
    (net (code "53") (name "Net-(IC23-RFinA)") (class "Default")
      (node (ref "C343") (pin "1") (pinfunction "1_1") (pintype "passive"))
      (node (ref "IC23") (pin "5") (pinfunction "RFinA_5") (pintype "passive"))
    )
    (net (code "54") (name "Net-(IC23-RFinB)") (class "Default")
      (node (ref "C358") (pin "1") (pinfunction "1_1") (pintype "passive"))
      (node (ref "IC23") (pin "4") (pinfunction "RFinB_4") (pintype "passive"))
    )
    (net (code "55") (name "Net-(IC23-Rset)") (class "Default")
      (node (ref "IC23") (pin "19") (pinfunction "Rset_19") (pintype "passive"))
      (node (ref "R161") (pin "1") (pinfunction "1_1") (pintype "passive"))
    )
    (net (code "56") (name "Net-(IC23-Vp)") (class "Default")
      (node (ref "C351") (pin "2") (pinfunction "2_2") (pintype "passive"))
      (node (ref "C352") (pin "1") (pinfunction "1_1") (pintype "passive"))
      (node (ref "IC23") (pin "18") (pinfunction "Vp_18") (pintype "passive"))
      (node (ref "R153") (pin "1") (pinfunction "1_1") (pintype "passive"))
    )
    (net (code "57") (name "Net-(IC24-CLKIN)") (class "Default")
      (node (ref "IC24") (pin "6") (pinfunction "CLKIN_6") (pintype "passive"))
      (node (ref "R155") (pin "2") (pinfunction "2_2") (pintype "passive"))
      (node (ref "R158") (pin "1") (pinfunction "1_1") (pintype "passive"))
    )
    (net (code "58") (name "Net-(J18-X)") (class "Default")
      (node (ref "J18") (pin "1") (pinfunction "X_1") (pintype "passive"))
      (node (ref "R151") (pin "1") (pinfunction "1_1") (pintype "passive"))
    )
    (net (code "59") (name "Net-(XO1-OUT)") (class "Default")
      (node (ref "R137") (pin "2") (pinfunction "2_2") (pintype "passive"))
      (node (ref "R143") (pin "2") (pinfunction "2_2") (pintype "passive"))
      (node (ref "XO1") (pin "4") (pinfunction "OUT_4") (pintype "passive"))
      (node (ref "XO2") (pin "3") (pinfunction "OUT_3") (pintype "passive"))
    )
    (net (code "60") (name "Net-(XO1-TRI-ST.)") (class "Default")
      (node (ref "R138") (pin "1") (pinfunction "1_1") (pintype "passive"))
      (node (ref "XO1") (pin "6") (pinfunction "TRI-ST._6") (pintype "passive"))
    )
    (net (code "61") (name "Net-(XO1-VDD)") (class "Default")
      (node (ref "C326") (pin "2") (pinfunction "2_2") (pintype "passive"))
      (node (ref "C327") (pin "2") (pinfunction "2_2") (pintype "passive"))
      (node (ref "FR49") (pin "1") (pinfunction "1_1") (pintype "passive"))
      (node (ref "R138") (pin "2") (pinfunction "2_2") (pintype "passive"))
      (node (ref "XO1") (pin "5") (pinfunction "VDD_5") (pintype "passive"))
      (node (ref "XO2") (pin "4") (pinfunction "VDD_4") (pintype "passive"))
    )
    (net (code "62") (name "VCC1P8") (class "Default")
      (node (ref "C364") (pin "1") (pinfunction "1_1") (pintype "passive"))
      (node (ref "C365") (pin "1") (pinfunction "1_1") (pintype "passive"))
      (node (ref "C366") (pin "1") (pinfunction "1_1") (pintype "passive"))
      (node (ref "FR52") (pin "1") (pinfunction "1_1") (pintype "passive"))
      (node (ref "IC24") (pin "10") (pinfunction "VDDOB_10") (pintype "passive"))
      (node (ref "IC24") (pin "11") (pinfunction "VDDOA_11") (pintype "passive"))
      (node (ref "IC24") (pin "14") (pinfunction "VDDOD_14") (pintype "passive"))
    )
    (net (code "63") (name "VCC3P3_CLK") (class "Default")
      (node (ref "C345") (pin "2") (pinfunction "2_2") (pintype "passive"))
      (node (ref "C349") (pin "1") (pinfunction "1_1") (pintype "passive"))
      (node (ref "C350") (pin "1") (pinfunction "1_1") (pintype "passive"))
      (node (ref "C359") (pin "1") (pinfunction "1_1") (pintype "passive"))
      (node (ref "C360") (pin "1") (pinfunction "1_1") (pintype "passive"))
      (node (ref "FR49") (pin "2") (pinfunction "2_2") (pintype "passive"))
      (node (ref "FR51") (pin "1") (pinfunction "1_1") (pintype "passive"))
      (node (ref "FR54") (pin "1") (pinfunction "1_1") (pintype "passive"))
      (node (ref "FR55") (pin "1") (pinfunction "1_1") (pintype "passive"))
      (node (ref "IC23") (pin "16") (pinfunction "DVdd_16") (pintype "passive"))
      (node (ref "IC23") (pin "17") (pinfunction "DVdd_17") (pintype "passive"))
      (node (ref "IC24") (pin "18") (pinfunction "VDDOC_18") (pintype "passive"))
      (node (ref "IC24") (pin "20") (pinfunction "VDD_20") (pintype "passive"))
      (node (ref "R141") (pin "1") (pinfunction "1_1") (pintype "passive"))
      (node (ref "R153") (pin "2") (pinfunction "2_2") (pintype "passive"))
      (node (ref "R154") (pin "2") (pinfunction "2_2") (pintype "passive"))
    )
    (net (code "64") (name "VCC3P3_LMK") (class "Default")
      (node (ref "C334") (pin "2") (pinfunction "2_2") (pintype "passive"))
      (node (ref "C335") (pin "2") (pinfunction "2_2") (pintype "passive"))
      (node (ref "C336") (pin "2") (pinfunction "2_2") (pintype "passive"))
      (node (ref "C337") (pin "2") (pinfunction "2_2") (pintype "passive"))
      (node (ref "FR51") (pin "2") (pinfunction "2_2") (pintype "passive"))
      (node (ref "IC20") (pin "23") (pinfunction "Vdd_23") (pintype "passive"))
      (node (ref "IC20") (pin "8") (pinfunction "Vdd_8") (pintype "passive"))
      (node (ref "R136") (pin "2") (pinfunction "2_2") (pintype "passive"))
      (node (ref "R149") (pin "1") (pinfunction "1_1") (pintype "passive"))
    )
    (net (code "65") (name "VDIO_LMS_FPGA") (class "Default")
      (node (ref "FR50") (pin "1") (pinfunction "1_1") (pintype "passive"))
      (node (ref "R149") (pin "2") (pinfunction "2_2") (pintype "passive"))
    )
    (net (code "66") (name "VDIO_LMS_LMK") (class "Default")
      (node (ref "C329") (pin "2") (pinfunction "2_2") (pintype "passive"))
      (node (ref "C330") (pin "2") (pinfunction "2_2") (pintype "passive"))
      (node (ref "C331") (pin "2") (pinfunction "2_2") (pintype "passive"))
      (node (ref "C332") (pin "2") (pinfunction "2_2") (pintype "passive"))
      (node (ref "FR50") (pin "2") (pinfunction "2_2") (pintype "passive"))
      (node (ref "IC20") (pin "14") (pinfunction "Vddo_14") (pintype "passive"))
      (node (ref "IC20") (pin "18") (pinfunction "Vddo_18") (pintype "passive"))
    )
    (net (code "67") (name "unconnected-(IC20-OSCin-Pad9)") (class "Default")
      (node (ref "IC20") (pin "9") (pinfunction "OSCin_9") (pintype "passive+no_connect"))
    )
    (net (code "68") (name "unconnected-(IC20-OSCout-Pad10)") (class "Default")
      (node (ref "IC20") (pin "10") (pinfunction "OSCout_10") (pintype "passive+no_connect"))
    )
    (net (code "69") (name "unconnected-(IC24-INTR-Pad3)") (class "Default")
      (node (ref "IC24") (pin "3") (pinfunction "INTR_3") (pintype "passive+no_connect"))
    )
    (net (code "70") (name "unconnected-(XO1-T.S.-Pad3)") (class "Default")
      (node (ref "XO1") (pin "3") (pinfunction "T.S._3") (pintype "passive+no_connect"))
    )
  )
)
